# BPSensor_Board.net
KiCad netlist of a schematic drawn in Altium Designer
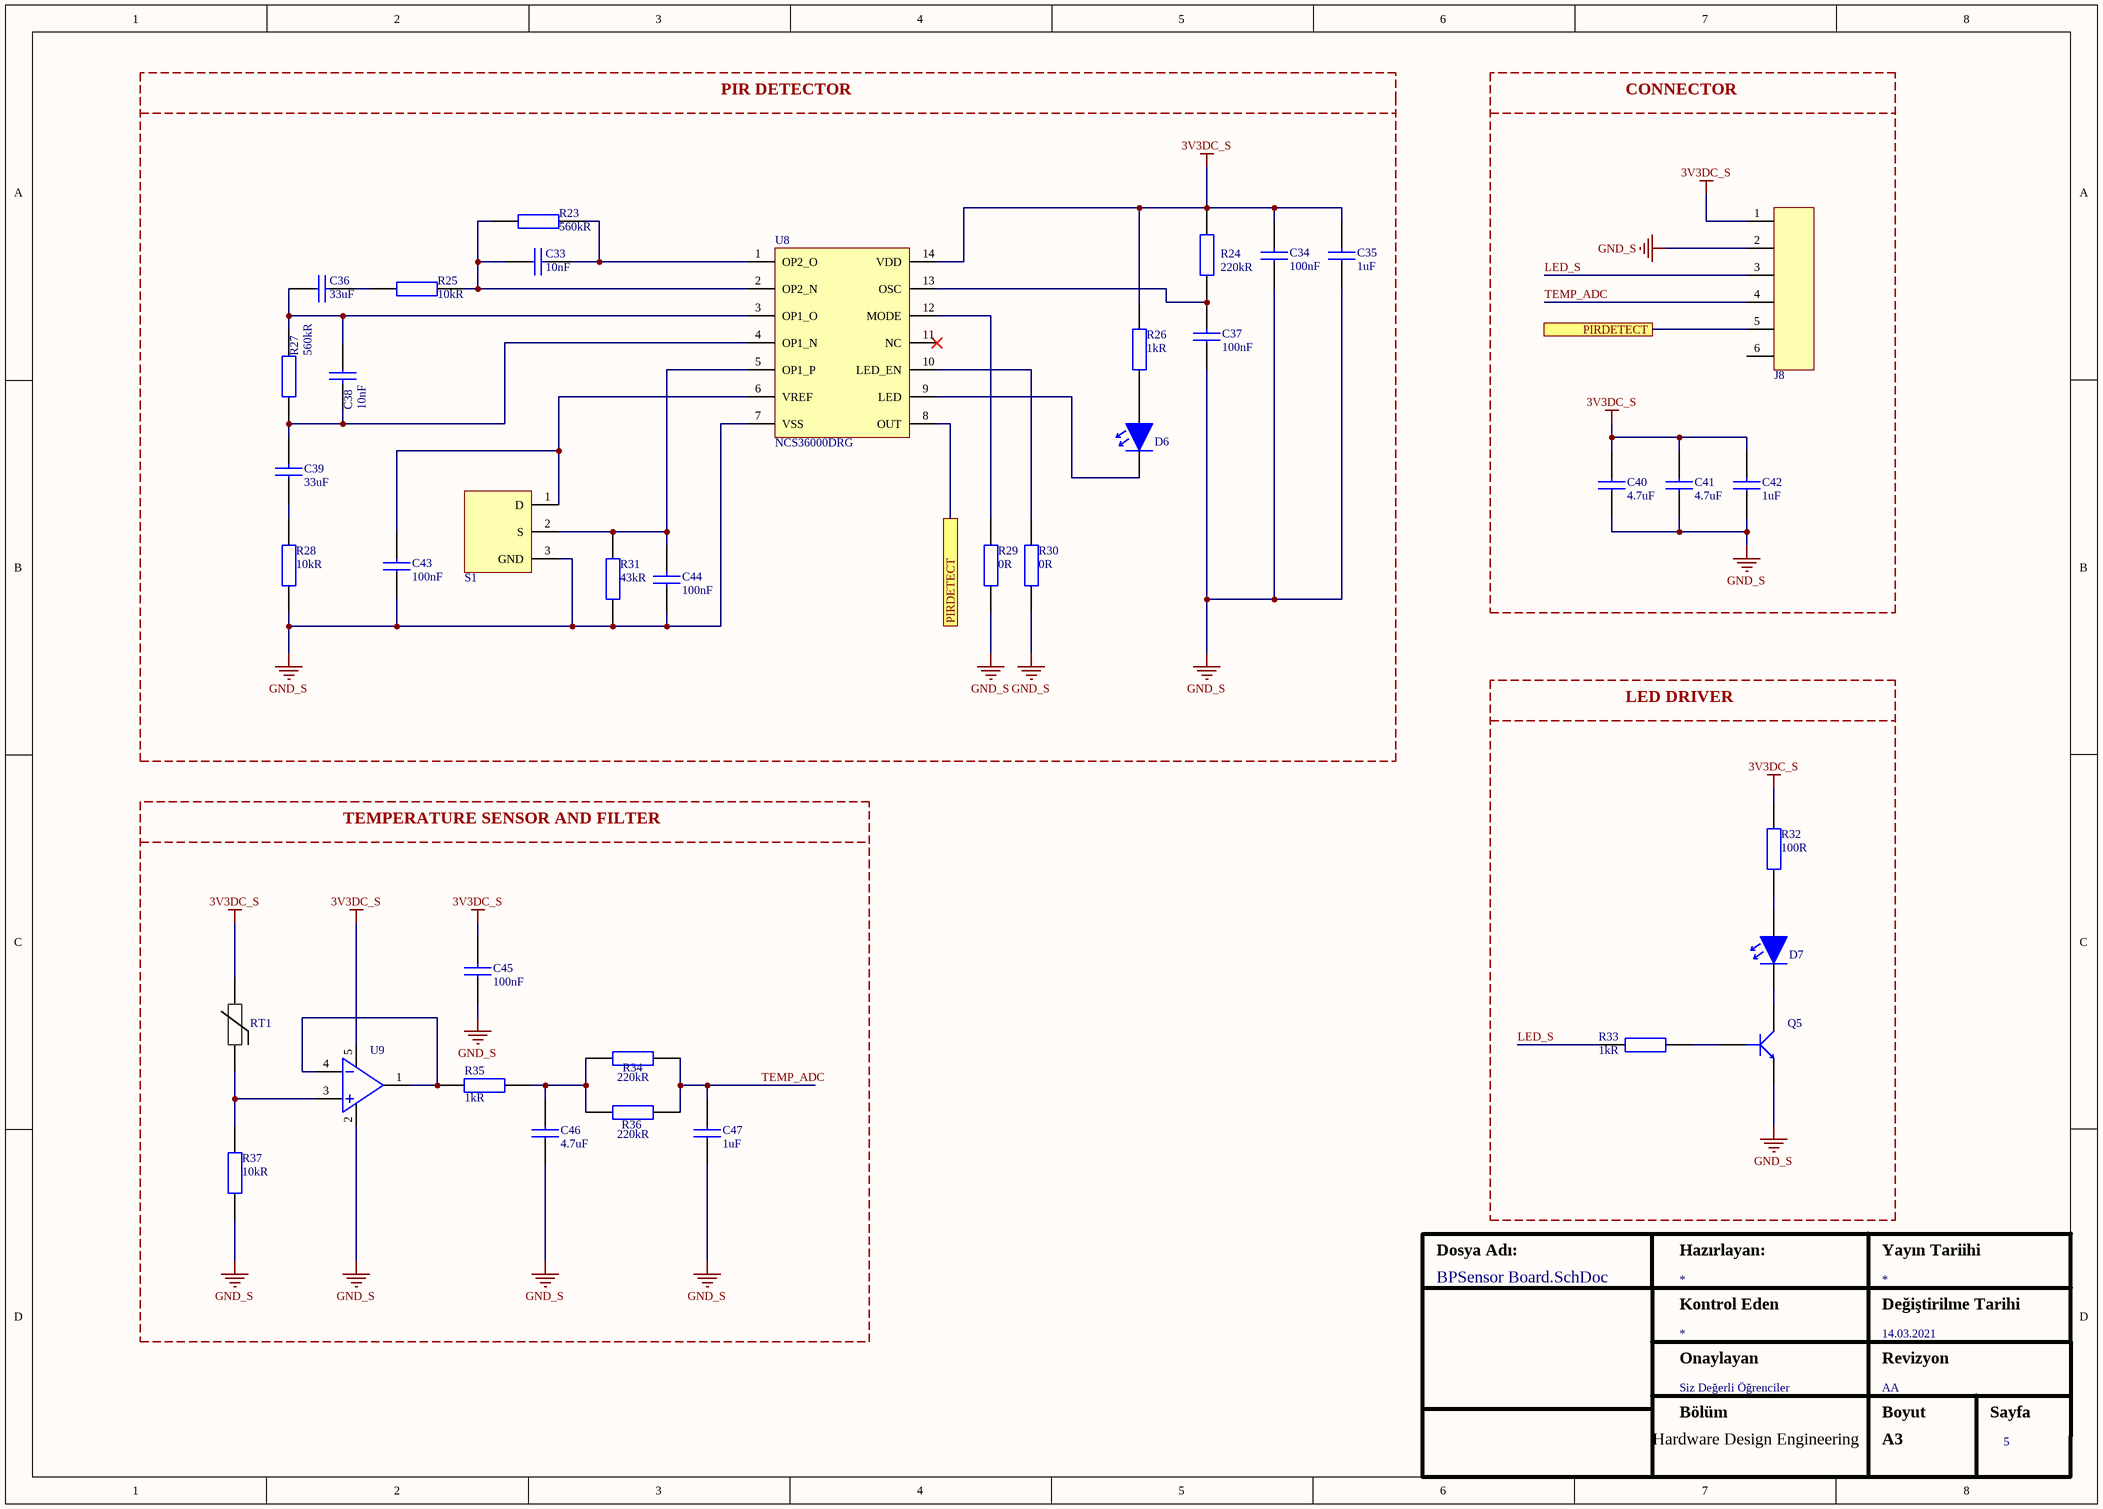
[diagram p0: BPSensor Board.SchDoc]

(export (version "E")
  (design (tool "Eeschema 10.0.6"))
  (components
    (comp (ref "C33")
      (value "0603B103K160CT")
      (footprint "CAP_0603")
      (description "CAP CER 10nF %10 0603")
      (fields
        (field (name "MANUFACTURER") "Walsin Technologies")
        (field (name "TOLERANCE") "10%")
        (field (name "CAPACITANCE") "10nF")
        (field (name "DESIGNED BY") "BERK")
      )
      (libsource (lib "UDEMY_Library") (part "CAP CER 10nF 0603"))
    )
    (comp (ref "C34")
      (value "C0603C104K5RACTU")
      (footprint "CAP_0603")
      (description "CAP CER 100nF %10 0603 SMD")
      (fields
        (field (name "MANUFACTURER") "KEMET")
        (field (name "TOLERANCE") "10%")
        (field (name "CAPACITANCE") "100nF")
        (field (name "DESIGNED BY") "BERK")
      )
      (libsource (lib "UDEMY_Library") (part "CAP CER 100nF 0603"))
    )
    (comp (ref "C35")
      (value "CL21B105KBFNNNE")
      (footprint "CAP_0805")
      (description "CAP CER 1uF %10 0805")
      (fields
        (field (name "MANUFACTURER") "Samsung")
        (field (name "TOLERANCE") "10%")
        (field (name "CAPACITANCE") "1uF")
        (field (name "DESIGNED BY") "BERK")
      )
      (libsource (lib "UDEMY_Library") (part "CAP CER 1uF 0805"))
    )
    (comp (ref "C36")
      (value "C3216X5R1E336M160AC")
      (footprint "CAP_1206")
      (description "CAP CER 33uF %20 1206 SMD")
      (fields
        (field (name "MANUFACTURER") "TDK")
        (field (name "TOLERANCE") "20%")
        (field (name "CAPACITANCE") "33uF")
        (field (name "DESIGNED BY") "BERK")
      )
      (libsource (lib "UDEMY_Library") (part "CAP CER 33uF 1206"))
    )
    (comp (ref "C37")
      (value "C0603C104K5RACTU")
      (footprint "CAP_0603")
      (description "CAP CER 100nF %10 0603 SMD")
      (fields
        (field (name "MANUFACTURER") "KEMET")
        (field (name "TOLERANCE") "10%")
        (field (name "CAPACITANCE") "100nF")
        (field (name "DESIGNED BY") "BERK")
      )
      (libsource (lib "UDEMY_Library") (part "CAP CER 100nF 0603"))
    )
    (comp (ref "C38")
      (value "0603B103K160CT")
      (footprint "CAP_0603")
      (description "CAP CER 10nF %10 0603")
      (fields
        (field (name "MANUFACTURER") "Walsin Technologies")
        (field (name "TOLERANCE") "10%")
        (field (name "CAPACITANCE") "10nF")
        (field (name "DESIGNED BY") "BERK")
      )
      (libsource (lib "UDEMY_Library") (part "CAP CER 10nF 0603"))
    )
    (comp (ref "C39")
      (value "C3216X5R1E336M160AC")
      (footprint "CAP_1206")
      (description "CAP CER 33uF %20 1206 SMD")
      (fields
        (field (name "MANUFACTURER") "TDK")
        (field (name "TOLERANCE") "20%")
        (field (name "CAPACITANCE") "33uF")
        (field (name "DESIGNED BY") "BERK")
      )
      (libsource (lib "UDEMY_Library") (part "CAP CER 33uF 1206"))
    )
    (comp (ref "C40")
      (value "CL21A475KAQNNNE")
      (footprint "CAP_0805")
      (description "CAP CER 4.7uF %10 0805")
      (fields
        (field (name "MANUFACTURER") "Samsung")
        (field (name "TOLERANCE") "10%")
        (field (name "CAPACITANCE") "4.7uF")
        (field (name "DESIGNED BY") "BERK")
      )
      (libsource (lib "UDEMY_Library") (part "CAP CER 4.7uF 0805"))
    )
    (comp (ref "C41")
      (value "CL21A475KAQNNNE")
      (footprint "CAP_0805")
      (description "CAP CER 4.7uF %10 0805")
      (fields
        (field (name "MANUFACTURER") "Samsung")
        (field (name "TOLERANCE") "10%")
        (field (name "CAPACITANCE") "4.7uF")
        (field (name "DESIGNED BY") "BERK")
      )
      (libsource (lib "UDEMY_Library") (part "CAP CER 4.7uF 0805"))
    )
    (comp (ref "C42")
      (value "CL21B105KBFNNNE")
      (footprint "CAP_0805")
      (description "CAP CER 1uF %10 0805")
      (fields
        (field (name "MANUFACTURER") "Samsung")
        (field (name "TOLERANCE") "10%")
        (field (name "CAPACITANCE") "1uF")
        (field (name "DESIGNED BY") "BERK")
      )
      (libsource (lib "UDEMY_Library") (part "CAP CER 1uF 0805"))
    )
    (comp (ref "C43")
      (value "C0603C104K5RACTU")
      (footprint "CAP_0603")
      (description "CAP CER 100nF %10 0603 SMD")
      (fields
        (field (name "MANUFACTURER") "KEMET")
        (field (name "TOLERANCE") "10%")
        (field (name "CAPACITANCE") "100nF")
        (field (name "DESIGNED BY") "BERK")
      )
      (libsource (lib "UDEMY_Library") (part "CAP CER 100nF 0603"))
    )
    (comp (ref "C44")
      (value "C0603C104K5RACTU")
      (footprint "CAP_0603")
      (description "CAP CER 100nF %10 0603 SMD")
      (fields
        (field (name "MANUFACTURER") "KEMET")
        (field (name "TOLERANCE") "10%")
        (field (name "CAPACITANCE") "100nF")
        (field (name "DESIGNED BY") "BERK")
      )
      (libsource (lib "UDEMY_Library") (part "CAP CER 100nF 0603"))
    )
    (comp (ref "C45")
      (value "C0603C104K5RACTU")
      (footprint "CAP_0603")
      (description "CAP CER 100nF %10 0603 SMD")
      (fields
        (field (name "MANUFACTURER") "KEMET")
        (field (name "TOLERANCE") "10%")
        (field (name "CAPACITANCE") "100nF")
        (field (name "DESIGNED BY") "BERK")
      )
      (libsource (lib "UDEMY_Library") (part "CAP CER 100nF 0603"))
    )
    (comp (ref "C46")
      (value "CL21A475KAQNNNE")
      (footprint "CAP_0805")
      (description "CAP CER 4.7uF %10 0805")
      (fields
        (field (name "MANUFACTURER") "Samsung")
        (field (name "TOLERANCE") "10%")
        (field (name "CAPACITANCE") "4.7uF")
        (field (name "DESIGNED BY") "BERK")
      )
      (libsource (lib "UDEMY_Library") (part "CAP CER 4.7uF 0805"))
    )
    (comp (ref "C47")
      (value "CL21B105KBFNNNE")
      (footprint "CAP_0805")
      (description "CAP CER 1uF %10 0805")
      (fields
        (field (name "MANUFACTURER") "Samsung")
        (field (name "TOLERANCE") "10%")
        (field (name "CAPACITANCE") "1uF")
        (field (name "DESIGNED BY") "BERK")
      )
      (libsource (lib "UDEMY_Library") (part "CAP CER 1uF 0805"))
    )
    (comp (ref "D6")
      (value "LTST-C171GKT")
      (footprint "LED_GREEN_0805")
      (description "Green 0805 130 º Min 5 mcd Typical 12 mcd Water Clear Lens SMT LED")
      (fields (field (name "MANUFACTURER") "Vishay Lite-On") (field (name "DESIGNED BY") "BERK"))
      (libsource (lib "UDEMY_Library") (part "LED GREEN 0805"))
    )
    (comp (ref "D7")
      (value "LH R974-LP-1")
      (footprint "LED_RED_0805")
      (description "LED Uni-Color Hyper Red 660nm 2-Pin Chip 0805(2012Metric) T/R")
      (fields (field (name "MANUFACTURER") "Osram Opto") (field (name "DESIGNED BY") "BERK"))
      (libsource (lib "UDEMY_Library") (part "LED RED 0805"))
    )
    (comp (ref "J8")
      (value "64800611622")
      (footprint "BPSchematic:64800611622")
      (description "1.50mm 6PIN Connector")
      (fields (field (name "MANUFACTURER") "Wurth Electronics"))
      (libsource (lib "UDEMY_Library") (part "64800611622_conn_6pin"))
    )
    (comp (ref "Q5")
      (value "MMBT3904-7-F")
      (footprint "SOT-23F")
      (description "Transistor General Purpose BJT NPN 40 Volt 0.2A Automotive 3-Pin SOT-23")
      (fields (field (name "MANUFACTURER") "Diodes Zetex") (field (name "DESIGNED BY") "BERK"))
      (libsource (lib "UDEMY_Library") (part "MMBT3904-7-F"))
    )
    (comp (ref "R23")
      (value "RC0603JR-07560KL")
      (footprint "RES_0603")
      (description "RES SMD 560K OHM 5% 1/10W 0603")
      (fields
        (field (name "MANUFACTURER") "Yageo")
        (field (name "TOLERANCE") "5%")
        (field (name "RESISTANCE") "560kR")
        (field (name "DESIGNED BY") "BERK")
      )
      (libsource (lib "UDEMY_Library") (part "RES 560K OHM 0603"))
    )
    (comp (ref "R24")
      (value "RC0603JR-07220KL")
      (footprint "RES_0603")
      (description "RES 220K %5 OHM 0603 SMD")
      (fields
        (field (name "MANUFACTURER") "Yageo")
        (field (name "TOLERANCE") "5%")
        (field (name "RESISTANCE") "220kR")
      )
      (libsource (lib "") (part "RES 220K OHM 0603_1"))
    )
    (comp (ref "R25")
      (value "RC0603FR-0710KL")
      (footprint "RES_0603")
      (description "RES 10K %1 OHM 0603 SMD")
      (fields
        (field (name "MANUFACTURER") "Yageo")
        (field (name "TOLERANCE") "1%")
        (field (name "RESISTANCE") "10kR")
        (field (name "DESIGNED BY") "BERK")
      )
      (libsource (lib "") (part "RES 10K OHM 0603_1"))
    )
    (comp (ref "R26")
      (value "RC0603FR-0710KL")
      (footprint "RES_0603")
      (description "RES 1K %1 OHM 0603 SMD")
      (fields
        (field (name "MANUFACTURER") "Yageo")
        (field (name "MANUFACTURER PART NUMBER") "RC0603JR-071KL")
        (field (name "RESISTANCE") "1kR")
        (field (name "DESIGNED BY") "BERK")
      )
      (libsource (lib "") (part "RES 1K OHM 0603_1"))
    )
    (comp (ref "R27")
      (value "RC0603JR-07560KL")
      (footprint "RES_0603")
      (description "RES SMD 560K OHM 5% 1/10W 0603")
      (fields
        (field (name "MANUFACTURER") "Yageo")
        (field (name "TOLERANCE") "5%")
        (field (name "RESISTANCE") "560kR")
        (field (name "DESIGNED BY") "BERK")
      )
      (libsource (lib "") (part "RES 560K OHM 0603_1"))
    )
    (comp (ref "R28")
      (value "RC0603FR-0710KL")
      (footprint "RES_0603")
      (description "RES 10K %1 OHM 0603 SMD")
      (fields
        (field (name "MANUFACTURER") "Yageo")
        (field (name "TOLERANCE") "1%")
        (field (name "RESISTANCE") "10kR")
        (field (name "DESIGNED BY") "BERK")
      )
      (libsource (lib "UDEMY_Library") (part "RES 10K OHM 0603"))
    )
    (comp (ref "R29")
      (value "RC0603JR-070RL")
      (footprint "RES_0603")
      (description "RES 0 %1 OHM 0603 SMD")
      (fields
        (field (name "MANUFACTURER") "Yageo")
        (field (name "TOLERANCE") "1%")
        (field (name "RESISTANCE") "0R")
        (field (name "DESIGNED BY") "BERK")
      )
      (libsource (lib "UDEMY_Library") (part "RES 0 OHM 0603"))
    )
    (comp (ref "R30")
      (value "RC0603JR-070RL")
      (footprint "RES_0603")
      (description "RES 0 %1 OHM 0603 SMD")
      (fields
        (field (name "MANUFACTURER") "Yageo")
        (field (name "TOLERANCE") "1%")
        (field (name "RESISTANCE") "0R")
        (field (name "DESIGNED BY") "BERK")
      )
      (libsource (lib "UDEMY_Library") (part "RES 0 OHM 0603"))
    )
    (comp (ref "R31")
      (value "RC0603JR-0743KL")
      (footprint "RES_0603")
      (description "RES 43K %5 OHM 0603 SMD")
      (fields
        (field (name "MANUFACTURER") "Yageo")
        (field (name "TOLERANCE") "5%")
        (field (name "RESISTANCE") "43kR")
        (field (name "DESIGNED BY") "BERK")
      )
      (libsource (lib "UDEMY_Library") (part "RES 43K OHM 0603"))
    )
    (comp (ref "R32")
      (value "RC0603JR-07100RL")
      (footprint "RES_0603")
      (description "RES 100 %5 OHM 0603 SMD")
      (fields
        (field (name "MANUFACTURER") "Yageo")
        (field (name "TOLERANCE") "5%")
        (field (name "RESISTANCE") "100R")
        (field (name "DESIGNED BY") "BERK")
      )
      (libsource (lib "UDEMY_Library") (part "RES 100 OHM 0603"))
    )
    (comp (ref "R33")
      (value "RC0603FR-0710KL")
      (footprint "RES_0603")
      (description "RES 1K %1 OHM 0603 SMD")
      (fields
        (field (name "MANUFACTURER") "Yageo")
        (field (name "MANUFACTURER PART NUMBER") "RC0603JR-071KL")
        (field (name "RESISTANCE") "1kR")
        (field (name "DESIGNED BY") "BERK")
      )
      (libsource (lib "UDEMY_Library") (part "RES 1K OHM 0603"))
    )
    (comp (ref "R34")
      (value "RC0603JR-07220KL")
      (footprint "RES_0603")
      (description "RES 220K %5 OHM 0603 SMD")
      (fields
        (field (name "MANUFACTURER") "Yageo")
        (field (name "TOLERANCE") "5%")
        (field (name "RESISTANCE") "220kR")
      )
      (libsource (lib "UDEMY_Library") (part "RES 220K OHM 0603"))
    )
    (comp (ref "R35")
      (value "RC0603FR-0710KL")
      (footprint "RES_0603")
      (description "RES 1K %1 OHM 0603 SMD")
      (fields
        (field (name "MANUFACTURER") "Yageo")
        (field (name "MANUFACTURER PART NUMBER") "RC0603JR-071KL")
        (field (name "RESISTANCE") "1kR")
        (field (name "DESIGNED BY") "BERK")
      )
      (libsource (lib "UDEMY_Library") (part "RES 1K OHM 0603"))
    )
    (comp (ref "R36")
      (value "RC0603JR-07220KL")
      (footprint "RES_0603")
      (description "RES 220K %5 OHM 0603 SMD")
      (fields
        (field (name "MANUFACTURER") "Yageo")
        (field (name "TOLERANCE") "5%")
        (field (name "RESISTANCE") "220kR")
      )
      (libsource (lib "UDEMY_Library") (part "RES 220K OHM 0603"))
    )
    (comp (ref "R37")
      (value "RC0603FR-0710KL")
      (footprint "RES_0603")
      (description "RES 10K %1 OHM 0603 SMD")
      (fields
        (field (name "MANUFACTURER") "Yageo")
        (field (name "TOLERANCE") "1%")
        (field (name "RESISTANCE") "10kR")
        (field (name "DESIGNED BY") "BERK")
      )
      (libsource (lib "UDEMY_Library") (part "RES 10K OHM 0603"))
    )
    (comp (ref "RT1")
      (value "TFPT1206L1002FM")
      (footprint "RES_1206")
      (description "Thermistor PTC 10K Ohm 1% 1206")
      (fields
        (field (name "MANUFACTURER") "Vishay Dale")
        (field (name "TOLERANCE") "1%")
        (field (name "DESIGNED BY") "BERK")
      )
      (libsource (lib "UDEMY_Library") (part "TFPT1206L1002FM"))
    )
    (comp (ref "S1")
      (value "LHI 878/3902")
      (footprint "LHI 878")
      (description "SENSOR PYRO DETECTOR DUAL MOTION")
      (fields (field (name "DESIGNED BY") "BERK"))
      (libsource (lib "UDEMY_Library") (part "LHI 878/3902"))
    )
    (comp (ref "U8")
      (value "NCS36000DRG")
      (footprint "SOIC14")
      (description "PIR Controller Low Noise Amplifiers and LDO Regulator 14-Pin SOIC N T/R")
      (fields (field (name "MANUFACTURER") "ON Semiconductor") (field (name "DESIGNED BY") "BERK"))
      (libsource (lib "UDEMY_Library") (part "NCS36000"))
    )
    (comp (ref "U9")
      (value "OPA314AIDBVR")
      (footprint "SOT23-5")
      (description "Op Amp OPA314")
      (fields (field (name "MANUFACTURER") "Texas Instruments") (field (name "DESIGNED BY") "BERK"))
      (libsource (lib "UDEMY_Library") (part "OPA314"))
    )
  )
  (nets
    (net (code "1") (name "/LED_S") (class "Default")
      (node (ref "J8") (pin "3") (pintype "power_in"))
      (node (ref "R33") (pin "1") (pinfunction "1_1") (pintype "passive"))
    )
    (net (code "2") (name "/PIRDETECT") (class "Default")
      (node (ref "J8") (pin "5") (pintype "power_in"))
      (node (ref "U8") (pin "8") (pinfunction "OUT_8") (pintype "passive"))
    )
    (net (code "3") (name "/TEMP_ADC") (class "Default")
      (node (ref "C47") (pin "2") (pinfunction "2_2") (pintype "passive"))
      (node (ref "J8") (pin "4") (pintype "power_in"))
      (node (ref "R34") (pin "2") (pinfunction "2_2") (pintype "passive"))
      (node (ref "R36") (pin "2") (pinfunction "2_2") (pintype "passive"))
    )
    (net (code "4") (name "3V3DC_S") (class "Default")
      (node (ref "C34") (pin "2") (pinfunction "2_2") (pintype "passive"))
      (node (ref "C35") (pin "2") (pinfunction "2_2") (pintype "passive"))
      (node (ref "C40") (pin "2") (pinfunction "2_2") (pintype "passive"))
      (node (ref "C41") (pin "2") (pinfunction "2_2") (pintype "passive"))
      (node (ref "C42") (pin "2") (pinfunction "2_2") (pintype "passive"))
      (node (ref "C45") (pin "2") (pinfunction "2_2") (pintype "passive"))
      (node (ref "J8") (pin "1") (pintype "power_in"))
      (node (ref "R24") (pin "2") (pinfunction "2_2") (pintype "passive"))
      (node (ref "R26") (pin "2") (pinfunction "2_2") (pintype "passive"))
      (node (ref "R32") (pin "2") (pinfunction "2_2") (pintype "passive"))
      (node (ref "RT1") (pin "2") (pinfunction "2_2") (pintype "passive"))
      (node (ref "U8") (pin "14") (pinfunction "VDD_14") (pintype "passive"))
      (node (ref "U9") (pin "5") (pinfunction "5_5") (pintype "passive"))
    )
    (net (code "5") (name "GND_S") (class "Default")
      (node (ref "C34") (pin "1") (pinfunction "1_1") (pintype "passive"))
      (node (ref "C35") (pin "1") (pinfunction "1_1") (pintype "passive"))
      (node (ref "C37") (pin "1") (pinfunction "1_1") (pintype "passive"))
      (node (ref "C40") (pin "1") (pinfunction "1_1") (pintype "passive"))
      (node (ref "C41") (pin "1") (pinfunction "1_1") (pintype "passive"))
      (node (ref "C42") (pin "1") (pinfunction "1_1") (pintype "passive"))
      (node (ref "C43") (pin "1") (pinfunction "1_1") (pintype "passive"))
      (node (ref "C44") (pin "1") (pinfunction "1_1") (pintype "passive"))
      (node (ref "C45") (pin "1") (pinfunction "1_1") (pintype "passive"))
      (node (ref "C46") (pin "1") (pinfunction "1_1") (pintype "passive"))
      (node (ref "C47") (pin "1") (pinfunction "1_1") (pintype "passive"))
      (node (ref "J8") (pin "2") (pintype "power_in"))
      (node (ref "Q5") (pin "2") (pinfunction "E_2") (pintype "power_in"))
      (node (ref "R28") (pin "1") (pinfunction "1_1") (pintype "passive"))
      (node (ref "R29") (pin "1") (pinfunction "1_1") (pintype "passive"))
      (node (ref "R30") (pin "1") (pinfunction "1_1") (pintype "passive"))
      (node (ref "R31") (pin "1") (pinfunction "1_1") (pintype "passive"))
      (node (ref "R37") (pin "1") (pinfunction "1_1") (pintype "passive"))
      (node (ref "S1") (pin "3") (pinfunction "GND_3") (pintype "passive"))
      (node (ref "U8") (pin "7") (pinfunction "VSS_7") (pintype "passive"))
      (node (ref "U9") (pin "2") (pinfunction "2_2") (pintype "passive"))
    )
    (net (code "6") (name "Net-(C36-Pad2)") (class "Default")
      (node (ref "C36") (pin "2") (pinfunction "2_2") (pintype "passive"))
      (node (ref "R25") (pin "1") (pinfunction "1_1") (pintype "passive"))
    )
    (net (code "7") (name "Net-(C39-Pad1)") (class "Default")
      (node (ref "C39") (pin "1") (pinfunction "1_1") (pintype "passive"))
      (node (ref "R28") (pin "2") (pinfunction "2_2") (pintype "passive"))
    )
    (net (code "8") (name "Net-(C46-Pad2)") (class "Default")
      (node (ref "C46") (pin "2") (pinfunction "2_2") (pintype "passive"))
      (node (ref "R34") (pin "1") (pinfunction "1_1") (pintype "passive"))
      (node (ref "R35") (pin "2") (pinfunction "2_2") (pintype "passive"))
      (node (ref "R36") (pin "1") (pinfunction "1_1") (pintype "passive"))
    )
    (net (code "9") (name "Net-(D6-Pad2)") (class "Default")
      (node (ref "D6") (pin "2") (pinfunction "2_2") (pintype "power_in"))
      (node (ref "R26") (pin "1") (pinfunction "1_1") (pintype "passive"))
    )
    (net (code "10") (name "Net-(D7-Pad2)") (class "Default")
      (node (ref "D7") (pin "2") (pinfunction "2_2") (pintype "power_in"))
      (node (ref "R32") (pin "1") (pinfunction "1_1") (pintype "passive"))
    )
    (net (code "11") (name "Net-(Q5-B)") (class "Default")
      (node (ref "Q5") (pin "1") (pinfunction "B_1") (pintype "power_in"))
      (node (ref "R33") (pin "2") (pinfunction "2_2") (pintype "passive"))
    )
    (net (code "12") (name "Net-(Q5-C)") (class "Default")
      (node (ref "D7") (pin "1") (pinfunction "1_1") (pintype "power_in"))
      (node (ref "Q5") (pin "3") (pinfunction "C_3") (pintype "power_in"))
    )
    (net (code "13") (name "Net-(R35-Pad1)") (class "Default")
      (node (ref "R35") (pin "1") (pinfunction "1_1") (pintype "passive"))
      (node (ref "U9") (pin "1") (pinfunction "1_1") (pintype "passive"))
      (node (ref "U9") (pin "4") (pinfunction "4_4") (pintype "passive"))
    )
    (net (code "14") (name "Net-(R37-Pad2)") (class "Default")
      (node (ref "R37") (pin "2") (pinfunction "2_2") (pintype "passive"))
      (node (ref "RT1") (pin "1") (pinfunction "1_1") (pintype "passive"))
      (node (ref "U9") (pin "3") (pinfunction "3_3") (pintype "passive"))
    )
    (net (code "15") (name "Net-(S1-D)") (class "Default")
      (node (ref "C43") (pin "2") (pinfunction "2_2") (pintype "passive"))
      (node (ref "S1") (pin "1") (pinfunction "D_1") (pintype "passive"))
      (node (ref "U8") (pin "6") (pinfunction "VREF_6") (pintype "passive"))
    )
    (net (code "16") (name "Net-(S1-S)") (class "Default")
      (node (ref "C44") (pin "2") (pinfunction "2_2") (pintype "passive"))
      (node (ref "R31") (pin "2") (pinfunction "2_2") (pintype "passive"))
      (node (ref "S1") (pin "2") (pinfunction "S_2") (pintype "passive"))
      (node (ref "U8") (pin "5") (pinfunction "OP1_P_5") (pintype "passive"))
    )
    (net (code "17") (name "Net-(U8-LED)") (class "Default")
      (node (ref "D6") (pin "1") (pinfunction "1_1") (pintype "power_in"))
      (node (ref "U8") (pin "9") (pinfunction "LED_9") (pintype "passive"))
    )
    (net (code "18") (name "Net-(U8-LED_EN)") (class "Default")
      (node (ref "R30") (pin "2") (pinfunction "2_2") (pintype "passive"))
      (node (ref "U8") (pin "10") (pinfunction "LED_EN_10") (pintype "passive"))
    )
    (net (code "19") (name "Net-(U8-MODE)") (class "Default")
      (node (ref "R29") (pin "2") (pinfunction "2_2") (pintype "passive"))
      (node (ref "U8") (pin "12") (pinfunction "MODE_12") (pintype "passive"))
    )
    (net (code "20") (name "Net-(U8-OP1_N)") (class "Default")
      (node (ref "C38") (pin "2") (pinfunction "2_2") (pintype "passive"))
      (node (ref "C39") (pin "2") (pinfunction "2_2") (pintype "passive"))
      (node (ref "R27") (pin "1") (pinfunction "1_1") (pintype "passive"))
      (node (ref "U8") (pin "4") (pinfunction "OP1_N_4") (pintype "passive"))
    )
    (net (code "21") (name "Net-(U8-OP1_O)") (class "Default")
      (node (ref "C36") (pin "1") (pinfunction "1_1") (pintype "passive"))
      (node (ref "C38") (pin "1") (pinfunction "1_1") (pintype "passive"))
      (node (ref "R27") (pin "2") (pinfunction "2_2") (pintype "passive"))
      (node (ref "U8") (pin "3") (pinfunction "OP1_O_3") (pintype "passive"))
    )
    (net (code "22") (name "Net-(U8-OP2_N)") (class "Default")
      (node (ref "C33") (pin "1") (pinfunction "1_1") (pintype "passive"))
      (node (ref "R23") (pin "1") (pinfunction "1_1") (pintype "passive"))
      (node (ref "R25") (pin "2") (pinfunction "2_2") (pintype "passive"))
      (node (ref "U8") (pin "2") (pinfunction "OP2_N_2") (pintype "passive"))
    )
    (net (code "23") (name "Net-(U8-OP2_O)") (class "Default")
      (node (ref "C33") (pin "2") (pinfunction "2_2") (pintype "passive"))
      (node (ref "R23") (pin "2") (pinfunction "2_2") (pintype "passive"))
      (node (ref "U8") (pin "1") (pinfunction "OP2_O_1") (pintype "passive"))
    )
    (net (code "24") (name "Net-(U8-OSC)") (class "Default")
      (node (ref "C37") (pin "2") (pinfunction "2_2") (pintype "passive"))
      (node (ref "R24") (pin "1") (pinfunction "1_1") (pintype "passive"))
      (node (ref "U8") (pin "13") (pinfunction "OSC_13") (pintype "passive"))
    )
    (net (code "25") (name "unconnected-(J8-Pad6)") (class "Default")
      (node (ref "J8") (pin "6") (pintype "power_in"))
    )
    (net (code "26") (name "unconnected-(U8-NC-Pad11)") (class "Default")
      (node (ref "U8") (pin "11") (pinfunction "NC_11") (pintype "passive+no_connect"))
    )
  )
)
